# PEXternalizer.net
KiCad netlist of a schematic drawn in EAGLE
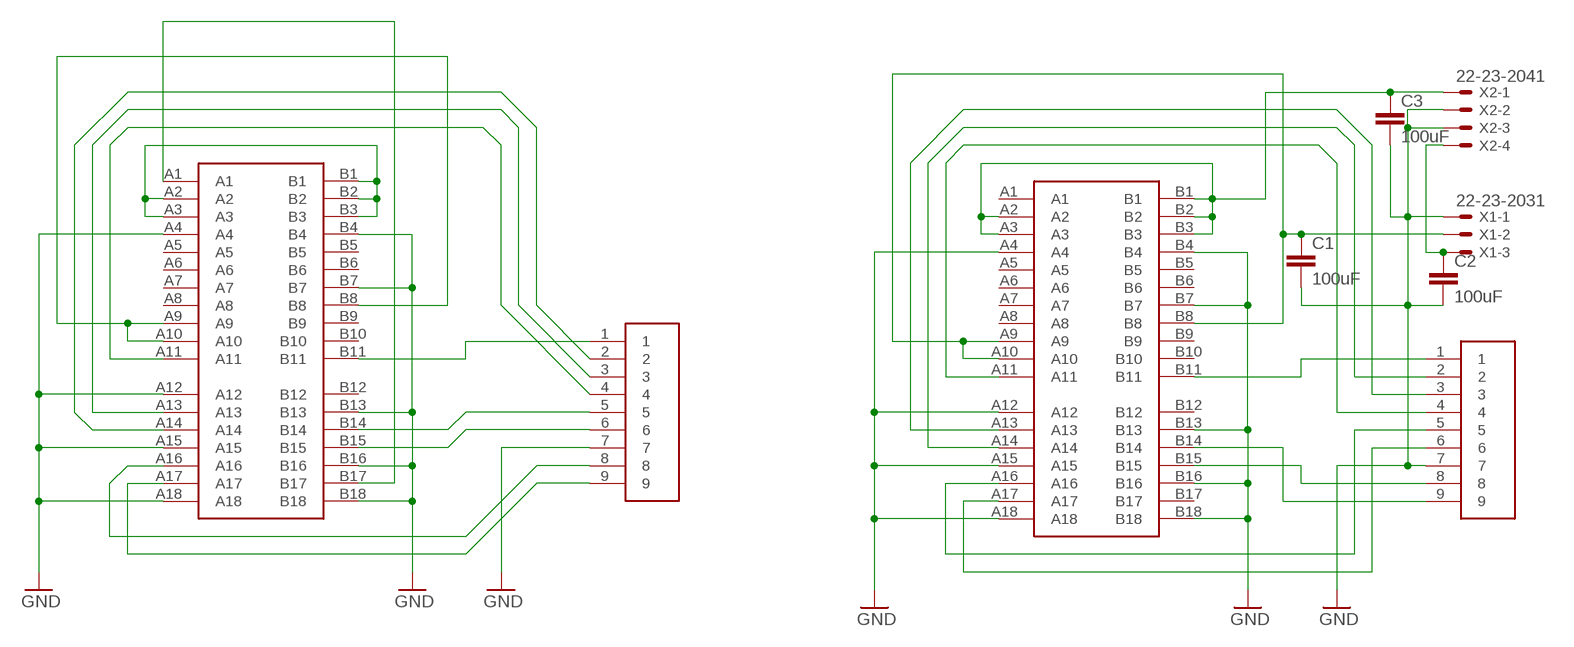
[diagram p0: schematic, sheet 1]

(export (version "E")
  (design (tool "Eeschema 10.0.6"))
  (components
    (comp (ref "3.3V")
      (value "PCI-E1XEDGE")
      (footprint "eagle-import:PCI-E_36_EDGE")
      (libsource (lib "eagle-import") (part "PCI-E1XEDGE"))
    )
    (comp (ref "3.3V1")
      (value "PCI-E1XCONN")
      (footprint "eagle-import:PCI-E_36_CONN")
      (libsource (lib "eagle-import") (part "PCI-E1XCONN"))
    )
    (comp (ref "C1")
      (value "100uF")
      (footprint "eagle-import:C5B2.5")
      (libsource (lib "eagle-import") (part "C5/2.5"))
    )
    (comp (ref "C2")
      (value "100uF")
      (footprint "eagle-import:C5B2.5")
      (libsource (lib "eagle-import") (part "C5/2.5"))
    )
    (comp (ref "C3")
      (value "100uF")
      (footprint "eagle-import:C2.5-2")
      (libsource (lib "eagle-import") (part "C2.5/2"))
    )
    (comp (ref "U$1")
      (value "USB3FLAT")
      (footprint "eagle-import:USB3_FLAT")
      (libsource (lib "eagle-import") (part "USB3FLAT"))
    )
    (comp (ref "U$2")
      (value "USB3FLAT")
      (footprint "eagle-import:USB3_FLAT")
      (libsource (lib "eagle-import") (part "USB3FLAT"))
    )
    (comp (ref "X1")
      (value "22-23-2031")
      (footprint "eagle-import:22-23-2031")
      (fields (field (name "MF") "MOLEX"))
      (libsource (lib "eagle-import") (part "22-23-2031"))
    )
    (comp (ref "X2")
      (value "22-23-2041")
      (footprint "eagle-import:22-23-2041")
      (fields (field (name "MF") "MOLEX"))
      (libsource (lib "eagle-import") (part "22-23-2041"))
    )
  )
  (nets
    (net (code "1") (name "GND") (class "Default")
      (node (ref "3.3V") (pin "A12") (pinfunction "A12_A12") (pintype "bidirectional"))
      (node (ref "3.3V") (pin "A15") (pinfunction "A15_A15") (pintype "bidirectional"))
      (node (ref "3.3V") (pin "A18") (pinfunction "A18_A18") (pintype "bidirectional"))
      (node (ref "3.3V") (pin "A4") (pinfunction "A4_A4") (pintype "bidirectional"))
      (node (ref "3.3V") (pin "B13") (pinfunction "B13_B13") (pintype "bidirectional"))
      (node (ref "3.3V") (pin "B16") (pinfunction "B16_B16") (pintype "bidirectional"))
      (node (ref "3.3V") (pin "B18") (pinfunction "B18_B18") (pintype "bidirectional"))
      (node (ref "3.3V") (pin "B4") (pinfunction "B4_B4") (pintype "bidirectional"))
      (node (ref "3.3V") (pin "B7") (pinfunction "B7_B7") (pintype "bidirectional"))
      (node (ref "3.3V1") (pin "A12") (pinfunction "A12_A12") (pintype "bidirectional"))
      (node (ref "3.3V1") (pin "A15") (pinfunction "A15_A15") (pintype "bidirectional"))
      (node (ref "3.3V1") (pin "A18") (pinfunction "A18_A18") (pintype "bidirectional"))
      (node (ref "3.3V1") (pin "A4") (pinfunction "A4_A4") (pintype "bidirectional"))
      (node (ref "3.3V1") (pin "B13") (pinfunction "B13_B13") (pintype "bidirectional"))
      (node (ref "3.3V1") (pin "B16") (pinfunction "B16_B16") (pintype "bidirectional"))
      (node (ref "3.3V1") (pin "B18") (pinfunction "B18_B18") (pintype "bidirectional"))
      (node (ref "3.3V1") (pin "B4") (pinfunction "B4_B4") (pintype "bidirectional"))
      (node (ref "3.3V1") (pin "B7") (pinfunction "B7_B7") (pintype "bidirectional"))
      (node (ref "C1") (pin "2") (pinfunction "2_2") (pintype "passive"))
      (node (ref "C2") (pin "2") (pinfunction "2_2") (pintype "passive"))
      (node (ref "C3") (pin "2") (pinfunction "2_2") (pintype "passive"))
      (node (ref "U$1") (pin "7") (pinfunction "7_7") (pintype "bidirectional"))
      (node (ref "U$2") (pin "7") (pinfunction "7_7") (pintype "bidirectional"))
      (node (ref "X1") (pin "1") (pinfunction "S_1") (pintype "passive"))
      (node (ref "X2") (pin "2") (pinfunction "S_2") (pintype "passive"))
      (node (ref "X2") (pin "3") (pinfunction "S_3") (pintype "passive"))
    )
    (net (code "2") (name "Net-(3.3V-PadA1)") (class "Default")
      (node (ref "3.3V") (pin "A1") (pinfunction "A1_A1") (pintype "bidirectional"))
      (node (ref "3.3V") (pin "B17") (pinfunction "B17_B17") (pintype "bidirectional"))
    )
    (net (code "3") (name "Net-(3.3V-PadA2)") (class "Default")
      (node (ref "3.3V") (pin "A2") (pinfunction "A2_A2") (pintype "bidirectional"))
      (node (ref "3.3V") (pin "A3") (pinfunction "A3_A3") (pintype "bidirectional"))
      (node (ref "3.3V") (pin "B1") (pinfunction "B1_B1") (pintype "bidirectional"))
      (node (ref "3.3V") (pin "B2") (pinfunction "B2_B2") (pintype "bidirectional"))
      (node (ref "3.3V") (pin "B3") (pinfunction "B3_B3") (pintype "bidirectional"))
    )
    (net (code "4") (name "Net-(3.3V-PadA10)") (class "Default")
      (node (ref "3.3V") (pin "A10") (pinfunction "A10_A10") (pintype "bidirectional"))
      (node (ref "3.3V") (pin "A9") (pinfunction "A9_A9") (pintype "bidirectional"))
      (node (ref "3.3V") (pin "B8") (pinfunction "B8_B8") (pintype "bidirectional"))
    )
    (net (code "5") (name "Net-(3.3V-PadA11)") (class "Default")
      (node (ref "3.3V") (pin "A11") (pinfunction "A11_A11") (pintype "bidirectional"))
      (node (ref "U$1") (pin "4") (pinfunction "4_4") (pintype "bidirectional"))
    )
    (net (code "6") (name "Net-(3.3V-PadA13)") (class "Default")
      (node (ref "3.3V") (pin "A13") (pinfunction "A13_A13") (pintype "bidirectional"))
      (node (ref "U$1") (pin "3") (pinfunction "3_3") (pintype "bidirectional"))
    )
    (net (code "7") (name "Net-(3.3V-PadA14)") (class "Default")
      (node (ref "3.3V") (pin "A14") (pinfunction "A14_A14") (pintype "bidirectional"))
      (node (ref "U$1") (pin "2") (pinfunction "2_2") (pintype "bidirectional"))
    )
    (net (code "8") (name "Net-(3.3V-PadA16)") (class "Default")
      (node (ref "3.3V") (pin "A16") (pinfunction "A16_A16") (pintype "bidirectional"))
      (node (ref "U$1") (pin "8") (pinfunction "8_8") (pintype "bidirectional"))
    )
    (net (code "9") (name "Net-(3.3V-PadA17)") (class "Default")
      (node (ref "3.3V") (pin "A17") (pinfunction "A17_A17") (pintype "bidirectional"))
      (node (ref "U$1") (pin "9") (pinfunction "9_9") (pintype "bidirectional"))
    )
    (net (code "10") (name "Net-(3.3V-PadB11)") (class "Default")
      (node (ref "3.3V") (pin "B11") (pinfunction "B11_B11") (pintype "bidirectional"))
      (node (ref "U$1") (pin "1") (pinfunction "1_1") (pintype "bidirectional"))
    )
    (net (code "11") (name "Net-(3.3V-PadB14)") (class "Default")
      (node (ref "3.3V") (pin "B14") (pinfunction "B14_B14") (pintype "bidirectional"))
      (node (ref "U$1") (pin "5") (pinfunction "5_5") (pintype "bidirectional"))
    )
    (net (code "12") (name "Net-(3.3V-PadB15)") (class "Default")
      (node (ref "3.3V") (pin "B15") (pinfunction "B15_B15") (pintype "bidirectional"))
      (node (ref "U$1") (pin "6") (pinfunction "6_6") (pintype "bidirectional"))
    )
    (net (code "13") (name "Net-(3.3V1-PadA11)") (class "Default")
      (node (ref "3.3V1") (pin "A11") (pinfunction "A11_A11") (pintype "bidirectional"))
      (node (ref "U$2") (pin "4") (pinfunction "4_4") (pintype "bidirectional"))
    )
    (net (code "14") (name "Net-(3.3V1-PadA13)") (class "Default")
      (node (ref "3.3V1") (pin "A13") (pinfunction "A13_A13") (pintype "bidirectional"))
      (node (ref "U$2") (pin "3") (pinfunction "3_3") (pintype "bidirectional"))
    )
    (net (code "15") (name "Net-(3.3V1-PadA14)") (class "Default")
      (node (ref "3.3V1") (pin "A14") (pinfunction "A14_A14") (pintype "bidirectional"))
      (node (ref "U$2") (pin "2") (pinfunction "2_2") (pintype "bidirectional"))
    )
    (net (code "16") (name "Net-(3.3V1-PadA16)") (class "Default")
      (node (ref "3.3V1") (pin "A16") (pinfunction "A16_A16") (pintype "bidirectional"))
      (node (ref "U$2") (pin "5") (pinfunction "5_5") (pintype "bidirectional"))
    )
    (net (code "17") (name "Net-(3.3V1-PadA17)") (class "Default")
      (node (ref "3.3V1") (pin "A17") (pinfunction "A17_A17") (pintype "bidirectional"))
      (node (ref "U$2") (pin "6") (pinfunction "6_6") (pintype "bidirectional"))
    )
    (net (code "18") (name "Net-(3.3V1-PadB11)") (class "Default")
      (node (ref "3.3V1") (pin "B11") (pinfunction "B11_B11") (pintype "bidirectional"))
      (node (ref "U$2") (pin "1") (pinfunction "1_1") (pintype "bidirectional"))
    )
    (net (code "19") (name "Net-(3.3V1-PadB14)") (class "Default")
      (node (ref "3.3V1") (pin "B14") (pinfunction "B14_B14") (pintype "bidirectional"))
      (node (ref "U$2") (pin "9") (pinfunction "9_9") (pintype "bidirectional"))
    )
    (net (code "20") (name "Net-(3.3V1-PadB15)") (class "Default")
      (node (ref "3.3V1") (pin "B15") (pinfunction "B15_B15") (pintype "bidirectional"))
      (node (ref "U$2") (pin "8") (pinfunction "8_8") (pintype "bidirectional"))
    )
    (net (code "21") (name "Net-(X1B-S)") (class "Default")
      (node (ref "3.3V1") (pin "A10") (pinfunction "A10_A10") (pintype "bidirectional"))
      (node (ref "3.3V1") (pin "A9") (pinfunction "A9_A9") (pintype "bidirectional"))
      (node (ref "3.3V1") (pin "B8") (pinfunction "B8_B8") (pintype "bidirectional"))
      (node (ref "C1") (pin "1") (pinfunction "1_1") (pintype "passive"))
      (node (ref "X1") (pin "2") (pinfunction "S_2") (pintype "passive"))
    )
    (net (code "22") (name "Net-(X1C-S)") (class "Default")
      (node (ref "C2") (pin "1") (pinfunction "1_1") (pintype "passive"))
      (node (ref "X1") (pin "3") (pinfunction "S_3") (pintype "passive"))
      (node (ref "X2") (pin "4") (pinfunction "S_4") (pintype "passive"))
    )
    (net (code "23") (name "Net-(X2A-S)") (class "Default")
      (node (ref "3.3V1") (pin "A2") (pinfunction "A2_A2") (pintype "bidirectional"))
      (node (ref "3.3V1") (pin "A3") (pinfunction "A3_A3") (pintype "bidirectional"))
      (node (ref "3.3V1") (pin "B1") (pinfunction "B1_B1") (pintype "bidirectional"))
      (node (ref "3.3V1") (pin "B2") (pinfunction "B2_B2") (pintype "bidirectional"))
      (node (ref "3.3V1") (pin "B3") (pinfunction "B3_B3") (pintype "bidirectional"))
      (node (ref "C3") (pin "1") (pinfunction "1_1") (pintype "passive"))
      (node (ref "X2") (pin "1") (pinfunction "S_1") (pintype "passive"))
    )
    (net (code "24") (name "unconnected-(3.3V-PadA5)") (class "Default")
      (node (ref "3.3V") (pin "A5") (pinfunction "A5_A5") (pintype "bidirectional"))
    )
    (net (code "25") (name "unconnected-(3.3V-PadA6)") (class "Default")
      (node (ref "3.3V") (pin "A6") (pinfunction "A6_A6") (pintype "bidirectional"))
    )
    (net (code "26") (name "unconnected-(3.3V-PadA7)") (class "Default")
      (node (ref "3.3V") (pin "A7") (pinfunction "A7_A7") (pintype "bidirectional"))
    )
    (net (code "27") (name "unconnected-(3.3V-PadA8)") (class "Default")
      (node (ref "3.3V") (pin "A8") (pinfunction "A8_A8") (pintype "bidirectional"))
    )
    (net (code "28") (name "unconnected-(3.3V-PadB5)") (class "Default")
      (node (ref "3.3V") (pin "B5") (pinfunction "B5_B5") (pintype "bidirectional"))
    )
    (net (code "29") (name "unconnected-(3.3V-PadB6)") (class "Default")
      (node (ref "3.3V") (pin "B6") (pinfunction "B6_B6") (pintype "bidirectional"))
    )
    (net (code "30") (name "unconnected-(3.3V-PadB9)") (class "Default")
      (node (ref "3.3V") (pin "B9") (pinfunction "B9_B9") (pintype "bidirectional"))
    )
    (net (code "31") (name "unconnected-(3.3V-PadB10)") (class "Default")
      (node (ref "3.3V") (pin "B10") (pinfunction "B10_B10") (pintype "bidirectional"))
    )
    (net (code "32") (name "unconnected-(3.3V-PadB12)") (class "Default")
      (node (ref "3.3V") (pin "B12") (pinfunction "B12_B12") (pintype "bidirectional"))
    )
    (net (code "33") (name "unconnected-(3.3V1-PadA1)") (class "Default")
      (node (ref "3.3V1") (pin "A1") (pinfunction "A1_A1") (pintype "bidirectional"))
    )
    (net (code "34") (name "unconnected-(3.3V1-PadA5)") (class "Default")
      (node (ref "3.3V1") (pin "A5") (pinfunction "A5_A5") (pintype "bidirectional"))
    )
    (net (code "35") (name "unconnected-(3.3V1-PadA6)") (class "Default")
      (node (ref "3.3V1") (pin "A6") (pinfunction "A6_A6") (pintype "bidirectional"))
    )
    (net (code "36") (name "unconnected-(3.3V1-PadA7)") (class "Default")
      (node (ref "3.3V1") (pin "A7") (pinfunction "A7_A7") (pintype "bidirectional"))
    )
    (net (code "37") (name "unconnected-(3.3V1-PadA8)") (class "Default")
      (node (ref "3.3V1") (pin "A8") (pinfunction "A8_A8") (pintype "bidirectional"))
    )
    (net (code "38") (name "unconnected-(3.3V1-PadB5)") (class "Default")
      (node (ref "3.3V1") (pin "B5") (pinfunction "B5_B5") (pintype "bidirectional"))
    )
    (net (code "39") (name "unconnected-(3.3V1-PadB6)") (class "Default")
      (node (ref "3.3V1") (pin "B6") (pinfunction "B6_B6") (pintype "bidirectional"))
    )
    (net (code "40") (name "unconnected-(3.3V1-PadB9)") (class "Default")
      (node (ref "3.3V1") (pin "B9") (pinfunction "B9_B9") (pintype "bidirectional"))
    )
    (net (code "41") (name "unconnected-(3.3V1-PadB10)") (class "Default")
      (node (ref "3.3V1") (pin "B10") (pinfunction "B10_B10") (pintype "bidirectional"))
    )
    (net (code "42") (name "unconnected-(3.3V1-PadB12)") (class "Default")
      (node (ref "3.3V1") (pin "B12") (pinfunction "B12_B12") (pintype "bidirectional"))
    )
    (net (code "43") (name "unconnected-(3.3V1-PadB17)") (class "Default")
      (node (ref "3.3V1") (pin "B17") (pinfunction "B17_B17") (pintype "bidirectional"))
    )
  )
)
